# RS485.net
KiCad netlist of a schematic drawn in Altium Designer
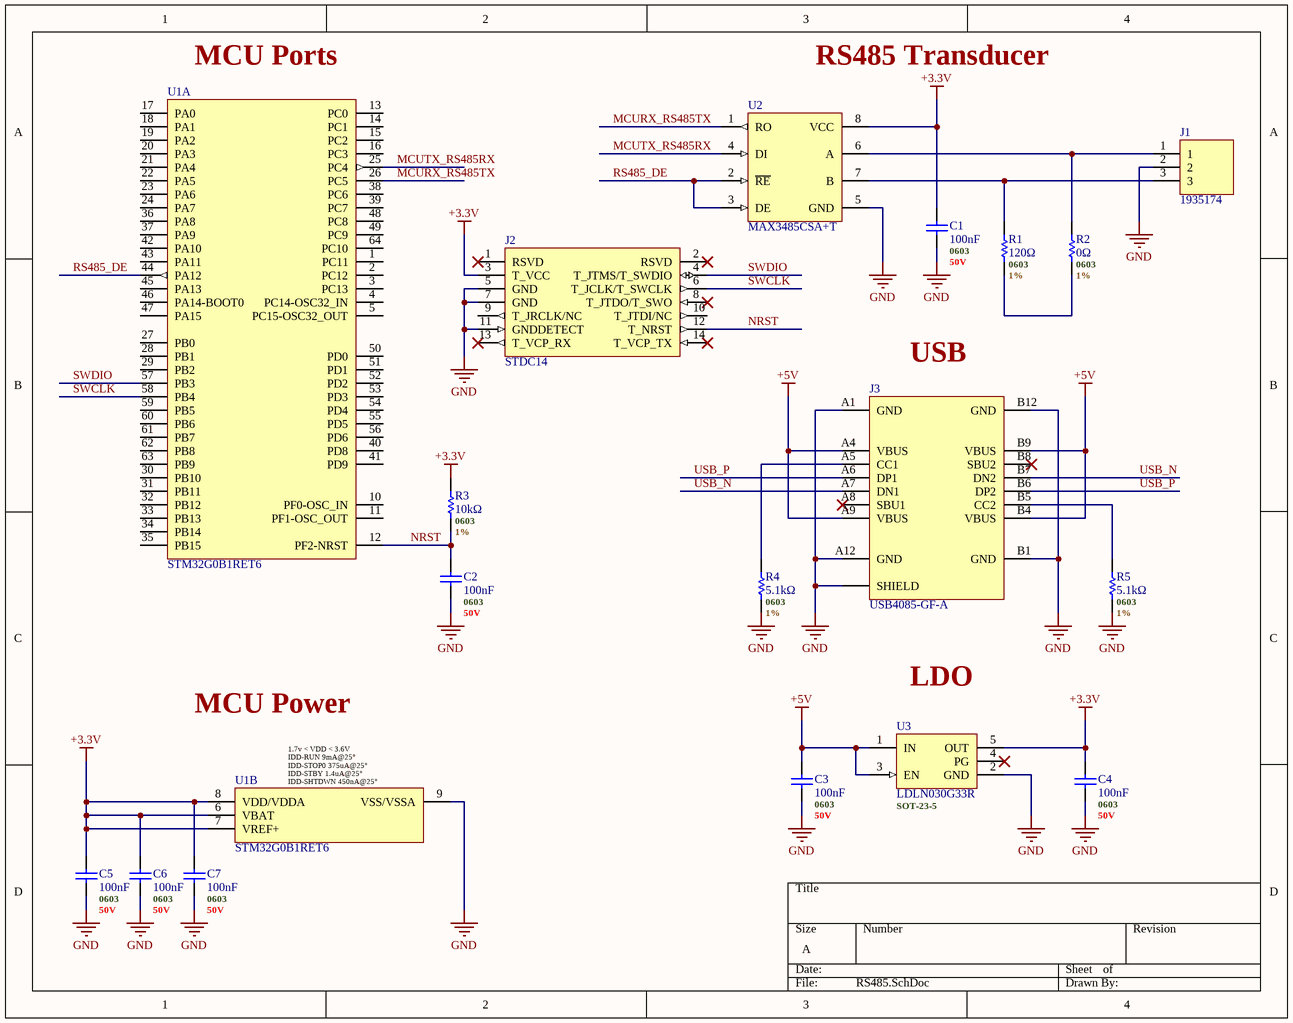
[diagram p0: RS485.SchDoc]

(export (version "E")
  (design (tool "Eeschema 10.0.6"))
  (components
    (comp (ref "C1")
      (value "100nF")
      (footprint "C0402 - MURATA")
      (description "Cap Ceramic 0.1uF 50V X7R 10% Pad SMD 0603 Soft Termination 125C Automotive T/R")
      (fields
        (field (name ".CASE/PACKAGE") "0603")
        (field (name ".RATED DC VOLTAGE (URDC)") "50V")
        (field (name "MANUFACTURER") "Murata")
        (field (name "MANUFACTURER PART NUMBER") "GCJ188R71H104KA12D")
      )
      (libsource (lib "CAP - GENERIC - 050525") (part "CAP - GENERIC"))
    )
    (comp (ref "C2")
      (value "100nF")
      (footprint "C0402 - MURATA")
      (description "Cap Ceramic 0.1uF 50V X7R 10% Pad SMD 0603 Soft Termination 125C Automotive T/R")
      (fields
        (field (name ".CASE/PACKAGE") "0603")
        (field (name ".RATED DC VOLTAGE (URDC)") "50V")
        (field (name "MANUFACTURER") "Murata")
        (field (name "MANUFACTURER PART NUMBER") "GCJ188R71H104KA12D")
      )
      (libsource (lib "CAP - GENERIC - 050525") (part "CAP - GENERIC"))
    )
    (comp (ref "C3")
      (value "100nF")
      (footprint "C0402 - MURATA")
      (description "Cap Ceramic 0.1uF 50V X7R 10% Pad SMD 0603 Soft Termination 125C Automotive T/R")
      (fields
        (field (name ".CASE/PACKAGE") "0603")
        (field (name ".RATED DC VOLTAGE (URDC)") "50V")
        (field (name "MANUFACTURER") "Murata")
        (field (name "MANUFACTURER PART NUMBER") "GCJ188R71H104KA12D")
      )
      (libsource (lib "CAP - GENERIC - 050525") (part "CAP - GENERIC"))
    )
    (comp (ref "C4")
      (value "100nF")
      (footprint "C0402 - MURATA")
      (description "Cap Ceramic 0.1uF 50V X7R 10% Pad SMD 0603 Soft Termination 125C Automotive T/R")
      (fields
        (field (name ".CASE/PACKAGE") "0603")
        (field (name ".RATED DC VOLTAGE (URDC)") "50V")
        (field (name "MANUFACTURER") "Murata")
        (field (name "MANUFACTURER PART NUMBER") "GCJ188R71H104KA12D")
      )
      (libsource (lib "CAP - GENERIC - 050525") (part "CAP - GENERIC"))
    )
    (comp (ref "C5")
      (value "100nF")
      (footprint "C0402 - MURATA")
      (description "Cap Ceramic 0.1uF 50V X7R 10% Pad SMD 0603 Soft Termination 125C Automotive T/R")
      (fields
        (field (name ".CASE/PACKAGE") "0603")
        (field (name ".RATED DC VOLTAGE (URDC)") "50V")
        (field (name "MANUFACTURER") "Murata")
        (field (name "MANUFACTURER PART NUMBER") "GCJ188R71H104KA12D")
      )
      (libsource (lib "CAP - GENERIC - 050525") (part "CAP - GENERIC"))
    )
    (comp (ref "C6")
      (value "100nF")
      (footprint "C0402 - MURATA")
      (description "Cap Ceramic 0.1uF 50V X7R 10% Pad SMD 0603 Soft Termination 125C Automotive T/R")
      (fields
        (field (name ".CASE/PACKAGE") "0603")
        (field (name ".RATED DC VOLTAGE (URDC)") "50V")
        (field (name "MANUFACTURER") "Murata")
        (field (name "MANUFACTURER PART NUMBER") "GCJ188R71H104KA12D")
      )
      (libsource (lib "CAP - GENERIC - 050525") (part "CAP - GENERIC"))
    )
    (comp (ref "C7")
      (value "100nF")
      (footprint "C0402 - MURATA")
      (description "Cap Ceramic 0.1uF 50V X7R 10% Pad SMD 0603 Soft Termination 125C Automotive T/R")
      (fields
        (field (name ".CASE/PACKAGE") "0603")
        (field (name ".RATED DC VOLTAGE (URDC)") "50V")
        (field (name "MANUFACTURER") "Murata")
        (field (name "MANUFACTURER PART NUMBER") "GCJ188R71H104KA12D")
      )
      (libsource (lib "CAP - GENERIC - 050525") (part "CAP - GENERIC"))
    )
    (comp (ref "J1")
      (value "1935174")
      (footprint "1935174 - PHOENIX")
      (description "Terminal Block; Printed Circuit; 16 A; 250 V; 5 mm; 3; 5 mm; Soldering Mount")
      (fields (field (name "MANUFACTURER") "Phoenix Contact") (field (name "VOLTAGE") "300V"))
      (libsource (lib "CONN - 1X3") (part "CONN 1X3"))
    )
    (comp (ref "J2")
      (value "STDC14")
      (footprint "FTSH-107-01-L-DV-K-P-TR")
      (fields
        (field (name "MANUFACTURER") "Samtec")
        (field (name "MANUFACTURER PART NUMBER") "FTSH-107-01-L-DV-K-P-TR")
      )
      (libsource (lib "DEBUG - STDC14 - 080124") (part "STDC14"))
    )
    (comp (ref "J3")
      (value "USB4085-GF-A")
      (footprint "USB4085-GF-A - GCT - 071422")
      (description "USB4085 Series 20 V PCB Top Mount USB 2.0 Type C Receptacle")
      (fields (field (name "MANUFACTURER") "Global Connector Technology"))
      (libsource (lib "USB - USB4085-GF-A - 070722") (part "USB4085-GF-A"))
    )
    (comp (ref "R1")
      (value "120Ω")
      (footprint "R0603 - YAGEO")
      (description "Res Thick Film 0603 120 Ohm 1% 0.1W(1/10W) ±100ppm/C Pad SMD T/R")
      (fields
        (field (name ".CASE/PACKAGE") "0603")
        (field (name ".TOLERANCE") "1%")
        (field (name "MANUFACTURER") "Yageo Group")
        (field (name "MANUFACTURER PART NUMBER") "RC0603FR-10120RL")
      )
      (libsource (lib "RESISTOR - GENERIC") (part "RESISTOR - GENERIC"))
    )
    (comp (ref "R2")
      (value "0Ω")
      (footprint "R0603 - YAGEO")
      (description "GENERAL PURPOSE CHIP RESISTOR Metal Glaze/thick Film, 0.1W, 0ohm, Surface Mount, 0603")
      (fields
        (field (name ".CASE/PACKAGE") "0603")
        (field (name ".TOLERANCE") "1%")
        (field (name "MANUFACTURER") "Yageo Group")
        (field (name "MANUFACTURER PART NUMBER") "RC0603JR-070RL")
      )
      (libsource (lib "RESISTOR - GENERIC - 050325") (part "RESISTOR - GENERIC"))
    )
    (comp (ref "R3")
      (value "10kΩ")
      (footprint "R0603 - YAGEO")
      (description "100mW Thick Film Resistors 75V ±100ppm/℃ ±1% 10kΩ 0603 Chip Resistor - Surface Mount ROHS")
      (fields
        (field (name ".CASE/PACKAGE") "0603")
        (field (name ".TOLERANCE") "1%")
        (field (name "MANUFACTURER") "Yageo Group")
        (field (name "MANUFACTURER PART NUMBER") "RC0603FR-0710KL")
      )
      (libsource (lib "RESISTOR - GENERIC - 050325") (part "RESISTOR - GENERIC"))
    )
    (comp (ref "R4")
      (value "5.1kΩ")
      (footprint "R0603 - YAGEO")
      (description "Res Thick Film 0603 5.1K Ohm 1% 0.1W(1/10W) ±100ppm/C Pad SMD T/R")
      (fields
        (field (name ".CASE/PACKAGE") "0603")
        (field (name ".TOLERANCE") "1%")
        (field (name "MANUFACTURER") "Yageo Group")
        (field (name "MANUFACTURER PART NUMBER") "RC0603FR-075K1L")
      )
      (libsource (lib "RESISTOR - GENERIC - 050325") (part "RESISTOR - GENERIC"))
    )
    (comp (ref "R5")
      (value "5.1kΩ")
      (footprint "R0603 - YAGEO")
      (description "Res Thick Film 0603 5.1K Ohm 1% 0.1W(1/10W) ±100ppm/C Pad SMD T/R")
      (fields
        (field (name ".CASE/PACKAGE") "0603")
        (field (name ".TOLERANCE") "1%")
        (field (name "MANUFACTURER") "Yageo Group")
        (field (name "MANUFACTURER PART NUMBER") "RC0603FR-075K1L")
      )
      (libsource (lib "RESISTOR - GENERIC - 050325") (part "RESISTOR - GENERIC"))
    )
    (comp (ref "U1")
      (value "STM32G0B1RET6")
      (footprint "64-LQFP - STM")
      (description "RISC Microcontroller, 32-Bit, FLASH, CORTEX-M0 CPU, 64MHz, CMOS, PQFP64")
      (fields (field (name "MANUFACTURER") "STMicroelectronics"))
      (libsource (lib "MCU - STM32G0B1RET6") (part "STM32G0B1RET6"))
    )
    (comp (ref "U2")
      (value "MAX3485CSA+T")
      (footprint "8-SOIC - ANALOG")
      (description "EAR99 MAX3485 Tape & Reel (TR) RS422RS485 interface transceiver 3.3V 0.000002A 4.9mm 22ns")
      (fields (field (name "MANUFACTURER") "Analog Devices"))
      (libsource (lib "MAX3485CSA+T - ANALOG") (part "MAX3485CSA+T"))
    )
    (comp (ref "U3")
      (value "LDLN030G33R")
      (footprint "TSOT-23-5 - STM")
      (description "LDO Regulator Pos 3.3V 0.3A 5-Pin TSOT-23 T/R")
      (fields (field (name "MANUFACTURER") "STMicroelectronics") (field (name ".CASE/PACKAGE") "SOT-23-5"))
      (libsource (lib "LDO - LDLN030G33R - 051725") (part "LDLN030G33R"))
    )
  )
  (nets
    (net (code "1") (name "+3.3V") (class "Default")
      (node (ref "C1") (pin "2") (pinfunction "2_2") (pintype "passive"))
      (node (ref "C4") (pin "2") (pinfunction "2_2") (pintype "passive"))
      (node (ref "C5") (pin "2") (pinfunction "2_2") (pintype "passive"))
      (node (ref "C6") (pin "2") (pinfunction "2_2") (pintype "passive"))
      (node (ref "C7") (pin "2") (pinfunction "2_2") (pintype "passive"))
      (node (ref "J2") (pin "3") (pinfunction "T_VCC_3") (pintype "power_in"))
      (node (ref "R3") (pin "2") (pinfunction "2_2") (pintype "passive"))
      (node (ref "U1") (pin "6") (pinfunction "VBAT_6") (pintype "power_in"))
      (node (ref "U1") (pin "7") (pinfunction "VREF+_7") (pintype "power_in"))
      (node (ref "U1") (pin "8") (pinfunction "VDD/VDDA_8") (pintype "power_in"))
      (node (ref "U2") (pin "8") (pinfunction "VCC_8") (pintype "power_in"))
      (node (ref "U3") (pin "5") (pinfunction "OUT_5") (pintype "power_in"))
    )
    (net (code "2") (name "+5V") (class "Default")
      (node (ref "C3") (pin "2") (pinfunction "2_2") (pintype "passive"))
      (node (ref "J3") (pin "A4") (pinfunction "VBUS_A4") (pintype "passive"))
      (node (ref "J3") (pin "A9") (pinfunction "VBUS_A9") (pintype "passive"))
      (node (ref "J3") (pin "B4") (pinfunction "VBUS_B4") (pintype "passive"))
      (node (ref "J3") (pin "B9") (pinfunction "VBUS_B9") (pintype "passive"))
      (node (ref "U3") (pin "1") (pinfunction "IN_1") (pintype "power_in"))
      (node (ref "U3") (pin "3") (pinfunction "EN_3") (pintype "input"))
    )
    (net (code "3") (name "/MCURX_RS485TX") (class "Default")
      (node (ref "U1") (pin "26") (pinfunction "PC5_26") (pintype "passive"))
      (node (ref "U2") (pin "1") (pinfunction "RO_1") (pintype "output"))
    )
    (net (code "4") (name "/MCUTX_RS485RX") (class "Default")
      (node (ref "U1") (pin "25") (pinfunction "PC4_25") (pintype "output"))
      (node (ref "U2") (pin "4") (pinfunction "DI_4") (pintype "input"))
    )
    (net (code "5") (name "/NRST") (class "Default")
      (node (ref "C2") (pin "2") (pinfunction "2_2") (pintype "passive"))
      (node (ref "J2") (pin "12") (pinfunction "T_NRST_12") (pintype "output"))
      (node (ref "R3") (pin "1") (pinfunction "1_1") (pintype "passive"))
      (node (ref "U1") (pin "12") (pinfunction "PF2-NRST_12") (pintype "passive"))
    )
    (net (code "6") (name "/RS485_DE") (class "Default")
      (node (ref "U1") (pin "44") (pinfunction "PA12_44") (pintype "output"))
      (node (ref "U2") (pin "2") (pinfunction "~{RE}_2") (pintype "input"))
      (node (ref "U2") (pin "3") (pinfunction "DE_3") (pintype "input"))
    )
    (net (code "7") (name "/SWCLK") (class "Default")
      (node (ref "J2") (pin "6") (pinfunction "T_JCLK/T_SWCLK_6") (pintype "output"))
      (node (ref "U1") (pin "58") (pinfunction "PB4_58") (pintype "passive"))
    )
    (net (code "8") (name "/SWDIO") (class "Default")
      (node (ref "J2") (pin "4") (pinfunction "T_JTMS/T_SWDIO_4") (pintype "bidirectional"))
      (node (ref "U1") (pin "57") (pinfunction "PB3_57") (pintype "passive"))
    )
    (net (code "9") (name "/USB_N") (class "Default")
      (node (ref "J3") (pin "A7") (pinfunction "DN1_A7") (pintype "passive"))
      (node (ref "J3") (pin "B7") (pinfunction "DN2_B7") (pintype "passive"))
    )
    (net (code "10") (name "/USB_P") (class "Default")
      (node (ref "J3") (pin "A6") (pinfunction "DP1_A6") (pintype "passive"))
      (node (ref "J3") (pin "B6") (pinfunction "DP2_B6") (pintype "passive"))
    )
    (net (code "11") (name "GND") (class "Default")
      (node (ref "C1") (pin "1") (pinfunction "1_1") (pintype "passive"))
      (node (ref "C2") (pin "1") (pinfunction "1_1") (pintype "passive"))
      (node (ref "C3") (pin "1") (pinfunction "1_1") (pintype "passive"))
      (node (ref "C4") (pin "1") (pinfunction "1_1") (pintype "passive"))
      (node (ref "C5") (pin "1") (pinfunction "1_1") (pintype "passive"))
      (node (ref "C6") (pin "1") (pinfunction "1_1") (pintype "passive"))
      (node (ref "C7") (pin "1") (pinfunction "1_1") (pintype "passive"))
      (node (ref "J1") (pin "2") (pinfunction "2_2") (pintype "passive"))
      (node (ref "J2") (pin "11") (pinfunction "GNDDETECT_11") (pintype "input"))
      (node (ref "J2") (pin "5") (pinfunction "GND_5") (pintype "power_in"))
      (node (ref "J2") (pin "7") (pinfunction "GND_7") (pintype "power_in"))
      (node (ref "J3") (pin "A1") (pinfunction "GND_A1") (pintype "passive"))
      (node (ref "J3") (pin "A12") (pinfunction "GND_A12") (pintype "passive"))
      (node (ref "J3") (pin "B1") (pinfunction "GND_B1") (pintype "passive"))
      (node (ref "J3") (pin "B12") (pinfunction "GND_B12") (pintype "passive"))
      (node (ref "J3") (pin "SHIELD") (pinfunction "SHIELD_SHIELD") (pintype "passive"))
      (node (ref "R4") (pin "1") (pinfunction "1_1") (pintype "passive"))
      (node (ref "R5") (pin "1") (pinfunction "1_1") (pintype "passive"))
      (node (ref "U1") (pin "9") (pinfunction "VSS/VSSA_9") (pintype "power_in"))
      (node (ref "U2") (pin "5") (pinfunction "GND_5") (pintype "power_in"))
      (node (ref "U3") (pin "2") (pinfunction "GND_2") (pintype "power_in"))
    )
    (net (code "12") (name "Net-(J3-CC1)") (class "Default")
      (node (ref "J3") (pin "A5") (pinfunction "CC1_A5") (pintype "passive"))
      (node (ref "R4") (pin "2") (pinfunction "2_2") (pintype "passive"))
    )
    (net (code "13") (name "Net-(J3-CC2)") (class "Default")
      (node (ref "J3") (pin "B5") (pinfunction "CC2_B5") (pintype "passive"))
      (node (ref "R5") (pin "2") (pinfunction "2_2") (pintype "passive"))
    )
    (net (code "14") (name "Net-(R1-Pad1)") (class "Default")
      (node (ref "R1") (pin "1") (pinfunction "1_1") (pintype "passive"))
      (node (ref "R2") (pin "1") (pinfunction "1_1") (pintype "passive"))
    )
    (net (code "15") (name "Net-(U2-A)") (class "Default")
      (node (ref "J1") (pin "1") (pinfunction "1_1") (pintype "passive"))
      (node (ref "R2") (pin "2") (pinfunction "2_2") (pintype "passive"))
      (node (ref "U2") (pin "6") (pinfunction "A_6") (pintype "passive"))
    )
    (net (code "16") (name "Net-(U2-B)") (class "Default")
      (node (ref "J1") (pin "3") (pinfunction "3_3") (pintype "passive"))
      (node (ref "R1") (pin "2") (pinfunction "2_2") (pintype "passive"))
      (node (ref "U2") (pin "7") (pinfunction "B_7") (pintype "passive"))
    )
    (net (code "17") (name "unconnected-(J2-RSVD-Pad1)") (class "Default")
      (node (ref "J2") (pin "1") (pinfunction "RSVD_1") (pintype "passive+no_connect"))
    )
    (net (code "18") (name "unconnected-(J2-RSVD-Pad2)") (class "Default")
      (node (ref "J2") (pin "2") (pinfunction "RSVD_2") (pintype "passive+no_connect"))
    )
    (net (code "19") (name "unconnected-(J2-T_JRCLK{slash}NC-Pad9)") (class "Default")
      (node (ref "J2") (pin "9") (pinfunction "T_JRCLK/NC_9") (pintype "output"))
    )
    (net (code "20") (name "unconnected-(J2-T_JTDI{slash}NC-Pad10)") (class "Default")
      (node (ref "J2") (pin "10") (pinfunction "T_JTDI/NC_10") (pintype "output"))
    )
    (net (code "21") (name "unconnected-(J2-T_JTDO{slash}T_SWO-Pad8)") (class "Default")
      (node (ref "J2") (pin "8") (pinfunction "T_JTDO/T_SWO_8") (pintype "input+no_connect"))
    )
    (net (code "22") (name "unconnected-(J2-T_VCP_RX-Pad13)") (class "Default")
      (node (ref "J2") (pin "13") (pinfunction "T_VCP_RX_13") (pintype "output+no_connect"))
    )
    (net (code "23") (name "unconnected-(J2-T_VCP_TX-Pad14)") (class "Default")
      (node (ref "J2") (pin "14") (pinfunction "T_VCP_TX_14") (pintype "input+no_connect"))
    )
    (net (code "24") (name "unconnected-(J3-SBU1-PadA8)") (class "Default")
      (node (ref "J3") (pin "A8") (pinfunction "SBU1_A8") (pintype "passive+no_connect"))
    )
    (net (code "25") (name "unconnected-(J3-SBU2-PadB8)") (class "Default")
      (node (ref "J3") (pin "B8") (pinfunction "SBU2_B8") (pintype "passive+no_connect"))
    )
    (net (code "26") (name "unconnected-(U1A-PA0-Pad17)") (class "Default")
      (node (ref "U1") (pin "17") (pinfunction "PA0_17") (pintype "passive"))
    )
    (net (code "27") (name "unconnected-(U1A-PA1-Pad18)") (class "Default")
      (node (ref "U1") (pin "18") (pinfunction "PA1_18") (pintype "passive"))
    )
    (net (code "28") (name "unconnected-(U1A-PA2-Pad19)") (class "Default")
      (node (ref "U1") (pin "19") (pinfunction "PA2_19") (pintype "passive"))
    )
    (net (code "29") (name "unconnected-(U1A-PA3-Pad20)") (class "Default")
      (node (ref "U1") (pin "20") (pinfunction "PA3_20") (pintype "passive"))
    )
    (net (code "30") (name "unconnected-(U1A-PA4-Pad21)") (class "Default")
      (node (ref "U1") (pin "21") (pinfunction "PA4_21") (pintype "passive"))
    )
    (net (code "31") (name "unconnected-(U1A-PA5-Pad22)") (class "Default")
      (node (ref "U1") (pin "22") (pinfunction "PA5_22") (pintype "passive"))
    )
    (net (code "32") (name "unconnected-(U1A-PA6-Pad23)") (class "Default")
      (node (ref "U1") (pin "23") (pinfunction "PA6_23") (pintype "passive"))
    )
    (net (code "33") (name "unconnected-(U1A-PA7-Pad24)") (class "Default")
      (node (ref "U1") (pin "24") (pinfunction "PA7_24") (pintype "passive"))
    )
    (net (code "34") (name "unconnected-(U1A-PA8-Pad36)") (class "Default")
      (node (ref "U1") (pin "36") (pinfunction "PA8_36") (pintype "passive"))
    )
    (net (code "35") (name "unconnected-(U1A-PA9-Pad37)") (class "Default")
      (node (ref "U1") (pin "37") (pinfunction "PA9_37") (pintype "passive"))
    )
    (net (code "36") (name "unconnected-(U1A-PA10-Pad42)") (class "Default")
      (node (ref "U1") (pin "42") (pinfunction "PA10_42") (pintype "passive"))
    )
    (net (code "37") (name "unconnected-(U1A-PA11-Pad43)") (class "Default")
      (node (ref "U1") (pin "43") (pinfunction "PA11_43") (pintype "passive"))
    )
    (net (code "38") (name "unconnected-(U1A-PA13-Pad45)") (class "Default")
      (node (ref "U1") (pin "45") (pinfunction "PA13_45") (pintype "passive"))
    )
    (net (code "39") (name "unconnected-(U1A-PA14-BOOT0-Pad46)") (class "Default")
      (node (ref "U1") (pin "46") (pinfunction "PA14-BOOT0_46") (pintype "passive"))
    )
    (net (code "40") (name "unconnected-(U1A-PA15-Pad47)") (class "Default")
      (node (ref "U1") (pin "47") (pinfunction "PA15_47") (pintype "passive"))
    )
    (net (code "41") (name "unconnected-(U1A-PB0-Pad27)") (class "Default")
      (node (ref "U1") (pin "27") (pinfunction "PB0_27") (pintype "passive"))
    )
    (net (code "42") (name "unconnected-(U1A-PB1-Pad28)") (class "Default")
      (node (ref "U1") (pin "28") (pinfunction "PB1_28") (pintype "passive"))
    )
    (net (code "43") (name "unconnected-(U1A-PB2-Pad29)") (class "Default")
      (node (ref "U1") (pin "29") (pinfunction "PB2_29") (pintype "passive"))
    )
    (net (code "44") (name "unconnected-(U1A-PB5-Pad59)") (class "Default")
      (node (ref "U1") (pin "59") (pinfunction "PB5_59") (pintype "passive"))
    )
    (net (code "45") (name "unconnected-(U1A-PB6-Pad60)") (class "Default")
      (node (ref "U1") (pin "60") (pinfunction "PB6_60") (pintype "passive"))
    )
    (net (code "46") (name "unconnected-(U1A-PB7-Pad61)") (class "Default")
      (node (ref "U1") (pin "61") (pinfunction "PB7_61") (pintype "passive"))
    )
    (net (code "47") (name "unconnected-(U1A-PB8-Pad62)") (class "Default")
      (node (ref "U1") (pin "62") (pinfunction "PB8_62") (pintype "passive"))
    )
    (net (code "48") (name "unconnected-(U1A-PB9-Pad63)") (class "Default")
      (node (ref "U1") (pin "63") (pinfunction "PB9_63") (pintype "passive"))
    )
    (net (code "49") (name "unconnected-(U1A-PB10-Pad30)") (class "Default")
      (node (ref "U1") (pin "30") (pinfunction "PB10_30") (pintype "passive"))
    )
    (net (code "50") (name "unconnected-(U1A-PB11-Pad31)") (class "Default")
      (node (ref "U1") (pin "31") (pinfunction "PB11_31") (pintype "passive"))
    )
    (net (code "51") (name "unconnected-(U1A-PB12-Pad32)") (class "Default")
      (node (ref "U1") (pin "32") (pinfunction "PB12_32") (pintype "passive"))
    )
    (net (code "52") (name "unconnected-(U1A-PB13-Pad33)") (class "Default")
      (node (ref "U1") (pin "33") (pinfunction "PB13_33") (pintype "passive"))
    )
    (net (code "53") (name "unconnected-(U1A-PB14-Pad34)") (class "Default")
      (node (ref "U1") (pin "34") (pinfunction "PB14_34") (pintype "passive"))
    )
    (net (code "54") (name "unconnected-(U1A-PB15-Pad35)") (class "Default")
      (node (ref "U1") (pin "35") (pinfunction "PB15_35") (pintype "passive"))
    )
    (net (code "55") (name "unconnected-(U1A-PC0-Pad13)") (class "Default")
      (node (ref "U1") (pin "13") (pinfunction "PC0_13") (pintype "passive"))
    )
    (net (code "56") (name "unconnected-(U1A-PC1-Pad14)") (class "Default")
      (node (ref "U1") (pin "14") (pinfunction "PC1_14") (pintype "passive"))
    )
    (net (code "57") (name "unconnected-(U1A-PC2-Pad15)") (class "Default")
      (node (ref "U1") (pin "15") (pinfunction "PC2_15") (pintype "passive"))
    )
    (net (code "58") (name "unconnected-(U1A-PC3-Pad16)") (class "Default")
      (node (ref "U1") (pin "16") (pinfunction "PC3_16") (pintype "passive"))
    )
    (net (code "59") (name "unconnected-(U1A-PC6-Pad38)") (class "Default")
      (node (ref "U1") (pin "38") (pinfunction "PC6_38") (pintype "passive"))
    )
    (net (code "60") (name "unconnected-(U1A-PC7-Pad39)") (class "Default")
      (node (ref "U1") (pin "39") (pinfunction "PC7_39") (pintype "passive"))
    )
    (net (code "61") (name "unconnected-(U1A-PC8-Pad48)") (class "Default")
      (node (ref "U1") (pin "48") (pinfunction "PC8_48") (pintype "passive"))
    )
    (net (code "62") (name "unconnected-(U1A-PC9-Pad49)") (class "Default")
      (node (ref "U1") (pin "49") (pinfunction "PC9_49") (pintype "passive"))
    )
    (net (code "63") (name "unconnected-(U1A-PC10-Pad64)") (class "Default")
      (node (ref "U1") (pin "64") (pinfunction "PC10_64") (pintype "passive"))
    )
    (net (code "64") (name "unconnected-(U1A-PC11-Pad1)") (class "Default")
      (node (ref "U1") (pin "1") (pinfunction "PC11_1") (pintype "passive"))
    )
    (net (code "65") (name "unconnected-(U1A-PC12-Pad2)") (class "Default")
      (node (ref "U1") (pin "2") (pinfunction "PC12_2") (pintype "passive"))
    )
    (net (code "66") (name "unconnected-(U1A-PC13-Pad3)") (class "Default")
      (node (ref "U1") (pin "3") (pinfunction "PC13_3") (pintype "passive"))
    )
    (net (code "67") (name "unconnected-(U1A-PC14-OSC32_IN-Pad4)") (class "Default")
      (node (ref "U1") (pin "4") (pinfunction "PC14-OSC32_IN_4") (pintype "passive"))
    )
    (net (code "68") (name "unconnected-(U1A-PC15-OSC32_OUT-Pad5)") (class "Default")
      (node (ref "U1") (pin "5") (pinfunction "PC15-OSC32_OUT_5") (pintype "passive"))
    )
    (net (code "69") (name "unconnected-(U1A-PD0-Pad50)") (class "Default")
      (node (ref "U1") (pin "50") (pinfunction "PD0_50") (pintype "passive"))
    )
    (net (code "70") (name "unconnected-(U1A-PD1-Pad51)") (class "Default")
      (node (ref "U1") (pin "51") (pinfunction "PD1_51") (pintype "passive"))
    )
    (net (code "71") (name "unconnected-(U1A-PD2-Pad52)") (class "Default")
      (node (ref "U1") (pin "52") (pinfunction "PD2_52") (pintype "passive"))
    )
    (net (code "72") (name "unconnected-(U1A-PD3-Pad53)") (class "Default")
      (node (ref "U1") (pin "53") (pinfunction "PD3_53") (pintype "passive"))
    )
    (net (code "73") (name "unconnected-(U1A-PD4-Pad54)") (class "Default")
      (node (ref "U1") (pin "54") (pinfunction "PD4_54") (pintype "passive"))
    )
    (net (code "74") (name "unconnected-(U1A-PD5-Pad55)") (class "Default")
      (node (ref "U1") (pin "55") (pinfunction "PD5_55") (pintype "passive"))
    )
    (net (code "75") (name "unconnected-(U1A-PD6-Pad56)") (class "Default")
      (node (ref "U1") (pin "56") (pinfunction "PD6_56") (pintype "passive"))
    )
    (net (code "76") (name "unconnected-(U1A-PD8-Pad40)") (class "Default")
      (node (ref "U1") (pin "40") (pinfunction "PD8_40") (pintype "passive"))
    )
    (net (code "77") (name "unconnected-(U1A-PD9-Pad41)") (class "Default")
      (node (ref "U1") (pin "41") (pinfunction "PD9_41") (pintype "passive"))
    )
    (net (code "78") (name "unconnected-(U1A-PF0-OSC_IN-Pad10)") (class "Default")
      (node (ref "U1") (pin "10") (pinfunction "PF0-OSC_IN_10") (pintype "passive"))
    )
    (net (code "79") (name "unconnected-(U1A-PF1-OSC_OUT-Pad11)") (class "Default")
      (node (ref "U1") (pin "11") (pinfunction "PF1-OSC_OUT_11") (pintype "passive"))
    )
    (net (code "80") (name "unconnected-(U3-PG-Pad4)") (class "Default")
      (node (ref "U3") (pin "4") (pinfunction "PG_4") (pintype "open_collector+no_connect"))
    )
  )
)
